# idealdiodeOR.net
KiCad netlist of a schematic drawn in Altium Designer
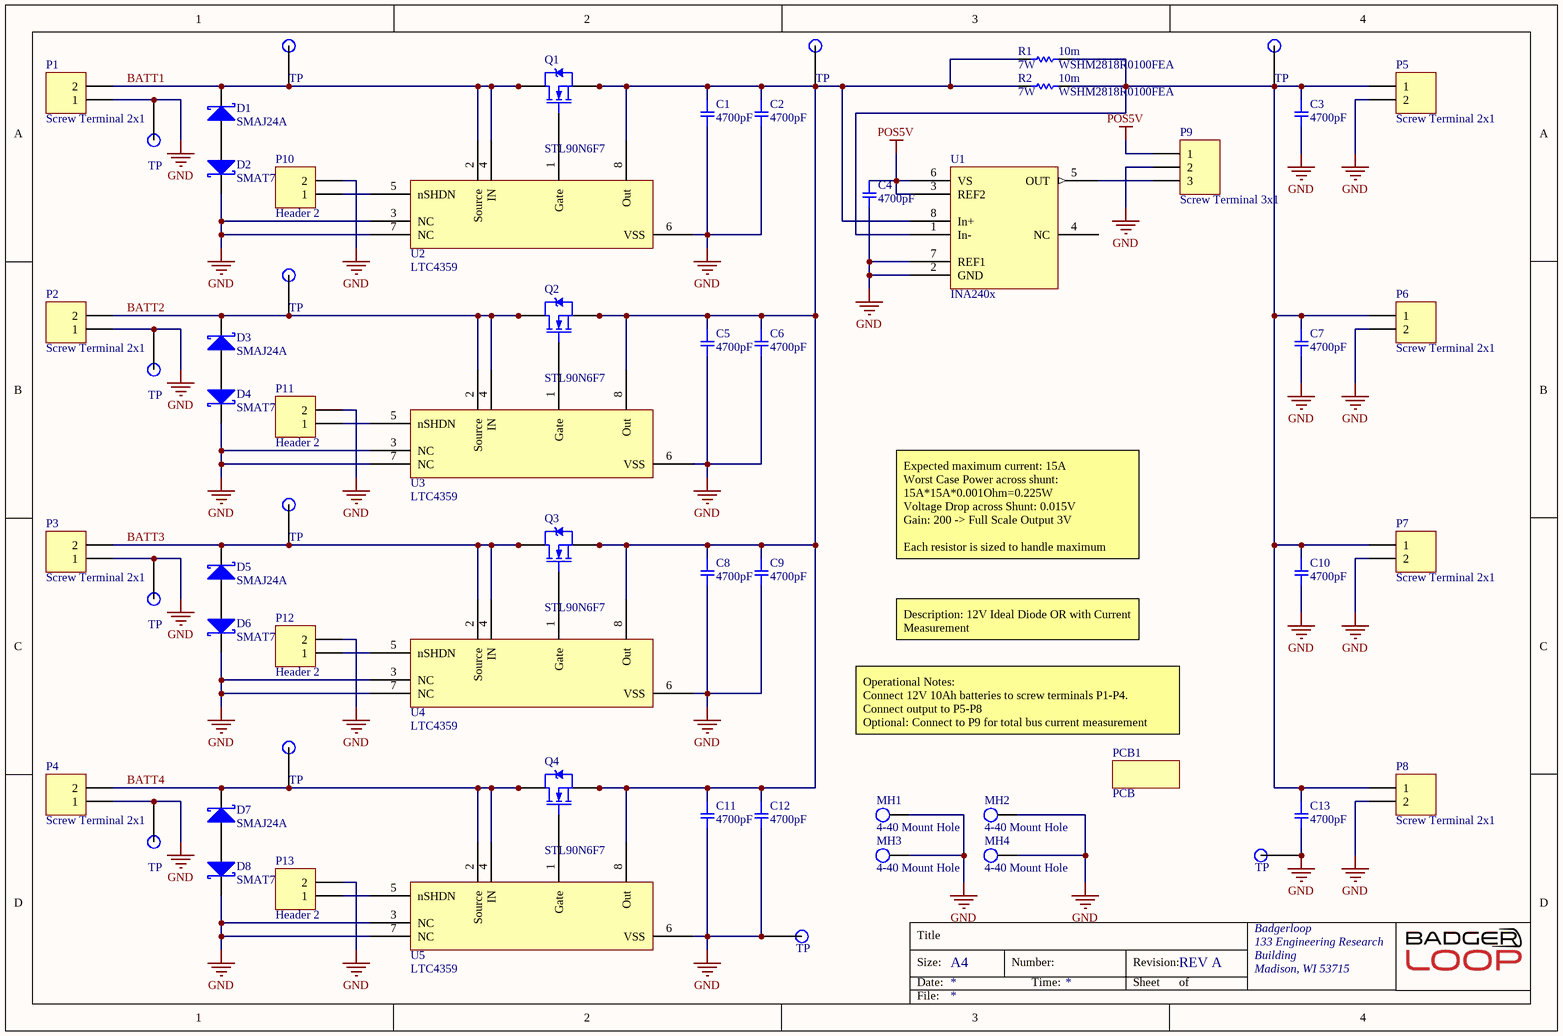
[diagram p0: idealdiodeOR.SchDoc]

(export (version "E")
  (design (tool "Eeschema 10.0.6"))
  (components
    (comp (ref "C1")
      (value "4700pF")
      (footprint "SMD-1206C")
      (description "CAP CER 4700PF 630V X7R 1206")
      (fields
        (field (name "PART NUMBER") "GCJ31BR72J472KXJ1L")
        (field (name "MANUFACTURER") "Murata Electronics North America")
      )
      (libsource (lib "capacitor") (part "GCJ31BR72J472KXJ1L"))
    )
    (comp (ref "C2")
      (value "4700pF")
      (footprint "SMD-1206C")
      (description "CAP CER 4700PF 630V X7R 1206")
      (fields
        (field (name "PART NUMBER") "GCJ31BR72J472KXJ1L")
        (field (name "MANUFACTURER") "Murata Electronics North America")
      )
      (libsource (lib "capacitor") (part "GCJ31BR72J472KXJ1L"))
    )
    (comp (ref "C3")
      (value "4700pF")
      (footprint "SMD-1206C")
      (description "CAP CER 4700PF 630V X7R 1206")
      (fields
        (field (name "PART NUMBER") "GCJ31BR72J472KXJ1L")
        (field (name "MANUFACTURER") "Murata Electronics North America")
      )
      (libsource (lib "capacitor") (part "GCJ31BR72J472KXJ1L"))
    )
    (comp (ref "C4")
      (value "4700pF")
      (footprint "SMD-1206C")
      (description "CAP CER 4700PF 630V X7R 1206")
      (fields
        (field (name "PART NUMBER") "GCJ31BR72J472KXJ1L")
        (field (name "MANUFACTURER") "Murata Electronics North America")
      )
      (libsource (lib "capacitor") (part "GCJ31BR72J472KXJ1L"))
    )
    (comp (ref "C5")
      (value "4700pF")
      (footprint "SMD-1206C")
      (description "CAP CER 4700PF 630V X7R 1206")
      (fields
        (field (name "PART NUMBER") "GCJ31BR72J472KXJ1L")
        (field (name "MANUFACTURER") "Murata Electronics North America")
      )
      (libsource (lib "capacitor") (part "GCJ31BR72J472KXJ1L"))
    )
    (comp (ref "C6")
      (value "4700pF")
      (footprint "SMD-1206C")
      (description "CAP CER 4700PF 630V X7R 1206")
      (fields
        (field (name "PART NUMBER") "GCJ31BR72J472KXJ1L")
        (field (name "MANUFACTURER") "Murata Electronics North America")
      )
      (libsource (lib "capacitor") (part "GCJ31BR72J472KXJ1L"))
    )
    (comp (ref "C7")
      (value "4700pF")
      (footprint "SMD-1206C")
      (description "CAP CER 4700PF 630V X7R 1206")
      (fields
        (field (name "PART NUMBER") "GCJ31BR72J472KXJ1L")
        (field (name "MANUFACTURER") "Murata Electronics North America")
      )
      (libsource (lib "capacitor") (part "GCJ31BR72J472KXJ1L"))
    )
    (comp (ref "C8")
      (value "4700pF")
      (footprint "SMD-1206C")
      (description "CAP CER 4700PF 630V X7R 1206")
      (fields
        (field (name "PART NUMBER") "GCJ31BR72J472KXJ1L")
        (field (name "MANUFACTURER") "Murata Electronics North America")
      )
      (libsource (lib "capacitor") (part "GCJ31BR72J472KXJ1L"))
    )
    (comp (ref "C9")
      (value "4700pF")
      (footprint "SMD-1206C")
      (description "CAP CER 4700PF 630V X7R 1206")
      (fields
        (field (name "PART NUMBER") "GCJ31BR72J472KXJ1L")
        (field (name "MANUFACTURER") "Murata Electronics North America")
      )
      (libsource (lib "capacitor") (part "GCJ31BR72J472KXJ1L"))
    )
    (comp (ref "C10")
      (value "4700pF")
      (footprint "SMD-1206C")
      (description "CAP CER 4700PF 630V X7R 1206")
      (fields
        (field (name "PART NUMBER") "GCJ31BR72J472KXJ1L")
        (field (name "MANUFACTURER") "Murata Electronics North America")
      )
      (libsource (lib "capacitor") (part "GCJ31BR72J472KXJ1L"))
    )
    (comp (ref "C11")
      (value "4700pF")
      (footprint "SMD-1206C")
      (description "CAP CER 4700PF 630V X7R 1206")
      (fields
        (field (name "PART NUMBER") "GCJ31BR72J472KXJ1L")
        (field (name "MANUFACTURER") "Murata Electronics North America")
      )
      (libsource (lib "capacitor") (part "GCJ31BR72J472KXJ1L"))
    )
    (comp (ref "C12")
      (value "4700pF")
      (footprint "SMD-1206C")
      (description "CAP CER 4700PF 630V X7R 1206")
      (fields
        (field (name "PART NUMBER") "GCJ31BR72J472KXJ1L")
        (field (name "MANUFACTURER") "Murata Electronics North America")
      )
      (libsource (lib "capacitor") (part "GCJ31BR72J472KXJ1L"))
    )
    (comp (ref "C13")
      (value "4700pF")
      (footprint "SMD-1206C")
      (description "CAP CER 4700PF 630V X7R 1206")
      (fields
        (field (name "PART NUMBER") "GCJ31BR72J472KXJ1L")
        (field (name "MANUFACTURER") "Murata Electronics North America")
      )
      (libsource (lib "capacitor") (part "GCJ31BR72J472KXJ1L"))
    )
    (comp (ref "D1")
      (value "SMAJ24A")
      (footprint "INDM5026X18N")
      (description "TVS DIODE 24V 38.9V DO214AC")
      (fields (field (name "MANUFACTURER") "LittelFuse Inc"))
      (libsource (lib "temp") (part "SMAJ24A"))
    )
    (comp (ref "D2")
      (value "SMAT70A")
      (footprint "SMAT70A")
      (description "TVS DIODE 70V 100V SMA")
      (fields (field (name "MANUFACTURER") "Diodes Incorporated"))
      (libsource (lib "temp") (part "SMAT70A"))
    )
    (comp (ref "D3")
      (value "SMAJ24A")
      (footprint "INDM5026X18N")
      (description "TVS DIODE 24V 38.9V DO214AC")
      (fields (field (name "MANUFACTURER") "LittelFuse Inc"))
      (libsource (lib "temp") (part "SMAJ24A"))
    )
    (comp (ref "D4")
      (value "SMAT70A")
      (footprint "SMAT70A")
      (description "TVS DIODE 70V 100V SMA")
      (fields (field (name "MANUFACTURER") "Diodes Incorporated"))
      (libsource (lib "temp") (part "SMAT70A"))
    )
    (comp (ref "D5")
      (value "SMAJ24A")
      (footprint "INDM5026X18N")
      (description "TVS DIODE 24V 38.9V DO214AC")
      (fields (field (name "MANUFACTURER") "LittelFuse Inc"))
      (libsource (lib "temp") (part "SMAJ24A"))
    )
    (comp (ref "D6")
      (value "SMAT70A")
      (footprint "SMAT70A")
      (description "TVS DIODE 70V 100V SMA")
      (fields (field (name "MANUFACTURER") "Diodes Incorporated"))
      (libsource (lib "temp") (part "SMAT70A"))
    )
    (comp (ref "D7")
      (value "SMAJ24A")
      (footprint "INDM5026X18N")
      (description "TVS DIODE 24V 38.9V DO214AC")
      (fields (field (name "MANUFACTURER") "LittelFuse Inc"))
      (libsource (lib "temp") (part "SMAJ24A"))
    )
    (comp (ref "D8")
      (value "SMAT70A")
      (footprint "SMAT70A")
      (description "TVS DIODE 70V 100V SMA")
      (fields (field (name "MANUFACTURER") "Diodes Incorporated"))
      (libsource (lib "temp") (part "SMAT70A"))
    )
    (comp (ref "MH1")
      (value "4-40 Mount Hole")
      (footprint "MH")
      (libsource (lib "misc") (part "4-40 Mount Hole"))
    )
    (comp (ref "MH2")
      (value "4-40 Mount Hole")
      (footprint "MH")
      (libsource (lib "misc") (part "4-40 Mount Hole"))
    )
    (comp (ref "MH3")
      (value "4-40 Mount Hole")
      (footprint "MH")
      (libsource (lib "misc") (part "4-40 Mount Hole"))
    )
    (comp (ref "MH4")
      (value "4-40 Mount Hole")
      (footprint "MH")
      (libsource (lib "misc") (part "4-40 Mount Hole"))
    )
    (comp (ref "P1")
      (value "Screw Terminal 2x1")
      (footprint "2POS TERM BLOCK")
      (description "Screw Terminal, 2-Pin")
      (libsource (lib "") (part "Screw Terminal 2x1_1"))
    )
    (comp (ref "P2")
      (value "Screw Terminal 2x1")
      (footprint "2POS TERM BLOCK")
      (description "Screw Terminal, 2-Pin")
      (libsource (lib "") (part "Screw Terminal 2x1_1"))
    )
    (comp (ref "P3")
      (value "Screw Terminal 2x1")
      (footprint "2POS TERM BLOCK")
      (description "Screw Terminal, 2-Pin")
      (libsource (lib "") (part "Screw Terminal 2x1_1"))
    )
    (comp (ref "P4")
      (value "Screw Terminal 2x1")
      (footprint "2POS TERM BLOCK")
      (description "Screw Terminal, 2-Pin")
      (libsource (lib "") (part "Screw Terminal 2x1_1"))
    )
    (comp (ref "P5")
      (value "Screw Terminal 2x1")
      (footprint "2POS TERM BLOCK")
      (description "Screw Terminal, 2-Pin")
      (libsource (lib "connector") (part "Screw Terminal 2x1"))
    )
    (comp (ref "P6")
      (value "Screw Terminal 2x1")
      (footprint "2POS TERM BLOCK")
      (description "Screw Terminal, 2-Pin")
      (libsource (lib "connector") (part "Screw Terminal 2x1"))
    )
    (comp (ref "P7")
      (value "Screw Terminal 2x1")
      (footprint "2POS TERM BLOCK")
      (description "Screw Terminal, 2-Pin")
      (libsource (lib "connector") (part "Screw Terminal 2x1"))
    )
    (comp (ref "P8")
      (value "Screw Terminal 2x1")
      (footprint "2POS TERM BLOCK")
      (description "Screw Terminal, 2-Pin")
      (libsource (lib "connector") (part "Screw Terminal 2x1"))
    )
    (comp (ref "P9")
      (value "Screw Terminal 3x1")
      (footprint "3POS TERM BLOCK")
      (description "Screw Terminal, 3-Pin")
      (fields (field (name "PUBLISHER") "Altium Limited"))
      (libsource (lib "connector") (part "Screw Terminal 3x1"))
    )
    (comp (ref "P10")
      (value "Header 2")
      (footprint "Pin Header 1x2 TH Pitch 2.54mm")
      (description "Header, 2-Pin")
      (fields (field (name "PUBLISHER") "Altium Limited"))
      (libsource (lib "altium-import") (part "root_2_Header 2_"))
    )
    (comp (ref "P11")
      (value "Header 2")
      (footprint "Pin Header 1x2 TH Pitch 2.54mm")
      (description "Header, 2-Pin")
      (fields (field (name "PUBLISHER") "Altium Limited"))
      (libsource (lib "altium-import") (part "root_2_Header 2_"))
    )
    (comp (ref "P12")
      (value "Header 2")
      (footprint "Pin Header 1x2 TH Pitch 2.54mm")
      (description "Header, 2-Pin")
      (fields (field (name "PUBLISHER") "Altium Limited"))
      (libsource (lib "altium-import") (part "root_2_Header 2_"))
    )
    (comp (ref "P13")
      (value "Header 2")
      (footprint "Pin Header 1x2 TH Pitch 2.54mm")
      (description "Header, 2-Pin")
      (fields (field (name "PUBLISHER") "Altium Limited"))
      (libsource (lib "altium-import") (part "root_2_Header 2_"))
    )
    (comp (ref "PCB1") (value "PCB") (footprint "PCB") (libsource (lib "temp") (part "PCB")))
    (comp (ref "Q1")
      (value "STL90N6F7")
      (footprint "DPAK228P991X238-4N")
      (description "MOSFET N-CH 60V 90A F7 8PWRFLAT")
      (fields (field (name "MANUFACTURER") "497-15913-2-ND"))
      (libsource (lib "temp") (part "STL90N6F7"))
    )
    (comp (ref "Q2")
      (value "STL90N6F7")
      (footprint "DPAK228P991X238-4N")
      (description "MOSFET N-CH 60V 90A F7 8PWRFLAT")
      (fields (field (name "MANUFACTURER") "497-15913-2-ND"))
      (libsource (lib "temp") (part "STL90N6F7"))
    )
    (comp (ref "Q3")
      (value "STL90N6F7")
      (footprint "DPAK228P991X238-4N")
      (description "MOSFET N-CH 60V 90A F7 8PWRFLAT")
      (fields (field (name "MANUFACTURER") "497-15913-2-ND"))
      (libsource (lib "temp") (part "STL90N6F7"))
    )
    (comp (ref "Q4")
      (value "STL90N6F7")
      (footprint "DPAK228P991X238-4N")
      (description "MOSFET N-CH 60V 90A F7 8PWRFLAT")
      (fields (field (name "MANUFACTURER") "497-15913-2-ND"))
      (libsource (lib "temp") (part "STL90N6F7"))
    )
    (comp (ref "R1")
      (value "WSHM2818R0100FEA")
      (footprint "CAPMP7146X15N")
      (description "RES 0.01 OHM 1% 7W 2818")
      (fields
        (field (name "MANUFACTURER") "Vishay Dale")
        (field (name "RESISTANCE") "10m")
        (field (name "POWER RATING") "7W")
      )
      (libsource (lib "temp") (part "WSHM2818R0100FEA"))
    )
    (comp (ref "R2")
      (value "WSHM2818R0100FEA")
      (footprint "CAPMP7146X15N")
      (description "RES 0.01 OHM 1% 7W 2818")
      (fields
        (field (name "MANUFACTURER") "Vishay Dale")
        (field (name "RESISTANCE") "10m")
        (field (name "POWER RATING") "7W")
      )
      (libsource (lib "temp") (part "WSHM2818R0100FEA"))
    )
    (comp (ref "TP1") (value "TP") (footprint "Test Point") (libsource (lib "misc") (part "TP")))
    (comp (ref "TP2") (value "TP") (footprint "Test Point") (libsource (lib "misc") (part "TP")))
    (comp (ref "TP3") (value "TP") (footprint "Test Point") (libsource (lib "misc") (part "TP")))
    (comp (ref "TP4") (value "TP") (footprint "Test Point") (libsource (lib "misc") (part "TP")))
    (comp (ref "TP5") (value "TP") (footprint "Test Point") (libsource (lib "misc") (part "TP")))
    (comp (ref "TP6") (value "TP") (footprint "Test Point") (libsource (lib "misc") (part "TP")))
    (comp (ref "TP7") (value "TP") (footprint "Test Point") (libsource (lib "misc") (part "TP")))
    (comp (ref "TP8") (value "TP") (footprint "Test Point") (libsource (lib "misc") (part "TP")))
    (comp (ref "TP9") (value "TP") (footprint "Test Point") (libsource (lib "misc") (part "TP")))
    (comp (ref "TP10") (value "TP") (footprint "Test Point") (libsource (lib "misc") (part "TP")))
    (comp (ref "TP11") (value "TP") (footprint "Test Point") (libsource (lib "misc") (part "TP")))
    (comp (ref "TP12") (value "TP") (footprint "Test Point") (libsource (lib "misc") (part "TP")))
    (comp (ref "U1")
      (value "INA240x")
      (footprint "SOIC127P600X175-8N")
      (description "IC AMP CURRENT SENSE 8-TSSOP")
      (fields (field (name "MANUFACTURER") "TI"))
      (libsource (lib "ic") (part "INA240x"))
    )
    (comp (ref "U2")
      (value "LTC4359")
      (footprint "8SOP")
      (description "IC OR CTRLR N+1 8MSOP")
      (fields (field (name "MANUFACTURER") "Analog Devices"))
      (libsource (lib "temp") (part "LTC4359"))
    )
    (comp (ref "U3")
      (value "LTC4359")
      (footprint "8SOP")
      (description "IC OR CTRLR N+1 8MSOP")
      (fields (field (name "MANUFACTURER") "Analog Devices"))
      (libsource (lib "temp") (part "LTC4359"))
    )
    (comp (ref "U4")
      (value "LTC4359")
      (footprint "8SOP")
      (description "IC OR CTRLR N+1 8MSOP")
      (fields (field (name "MANUFACTURER") "Analog Devices"))
      (libsource (lib "temp") (part "LTC4359"))
    )
    (comp (ref "U5")
      (value "LTC4359")
      (footprint "8SOP")
      (description "IC OR CTRLR N+1 8MSOP")
      (fields (field (name "MANUFACTURER") "Analog Devices"))
      (libsource (lib "temp") (part "LTC4359"))
    )
  )
  (nets
    (net (code "1") (name "/BATT1") (class "Default")
      (node (ref "D1") (pin "1") (pinfunction "A_1") (pintype "passive"))
      (node (ref "P1") (pin "2") (pinfunction "2_2") (pintype "passive"))
      (node (ref "Q1") (pin "5") (pinfunction "D_5") (pintype "passive"))
      (node (ref "Q1") (pin "6") (pinfunction "D_6") (pintype "passive"))
      (node (ref "Q1") (pin "7") (pinfunction "D_7") (pintype "passive"))
      (node (ref "Q1") (pin "8") (pinfunction "D_8") (pintype "passive"))
      (node (ref "TP1") (pin "1") (pinfunction "1_1") (pintype "passive"))
      (node (ref "U2") (pin "2") (pinfunction "Source_2") (pintype "passive"))
      (node (ref "U2") (pin "4") (pinfunction "IN_4") (pintype "passive"))
    )
    (net (code "2") (name "/BATT2") (class "Default")
      (node (ref "D3") (pin "1") (pinfunction "A_1") (pintype "passive"))
      (node (ref "P2") (pin "2") (pinfunction "2_2") (pintype "passive"))
      (node (ref "Q2") (pin "5") (pinfunction "D_5") (pintype "passive"))
      (node (ref "Q2") (pin "6") (pinfunction "D_6") (pintype "passive"))
      (node (ref "Q2") (pin "7") (pinfunction "D_7") (pintype "passive"))
      (node (ref "Q2") (pin "8") (pinfunction "D_8") (pintype "passive"))
      (node (ref "TP4") (pin "1") (pinfunction "1_1") (pintype "passive"))
      (node (ref "U3") (pin "2") (pinfunction "Source_2") (pintype "passive"))
      (node (ref "U3") (pin "4") (pinfunction "IN_4") (pintype "passive"))
    )
    (net (code "3") (name "/BATT3") (class "Default")
      (node (ref "D5") (pin "1") (pinfunction "A_1") (pintype "passive"))
      (node (ref "P3") (pin "2") (pinfunction "2_2") (pintype "passive"))
      (node (ref "Q3") (pin "5") (pinfunction "D_5") (pintype "passive"))
      (node (ref "Q3") (pin "6") (pinfunction "D_6") (pintype "passive"))
      (node (ref "Q3") (pin "7") (pinfunction "D_7") (pintype "passive"))
      (node (ref "Q3") (pin "8") (pinfunction "D_8") (pintype "passive"))
      (node (ref "TP6") (pin "1") (pinfunction "1_1") (pintype "passive"))
      (node (ref "U4") (pin "2") (pinfunction "Source_2") (pintype "passive"))
      (node (ref "U4") (pin "4") (pinfunction "IN_4") (pintype "passive"))
    )
    (net (code "4") (name "/BATT4") (class "Default")
      (node (ref "D7") (pin "1") (pinfunction "A_1") (pintype "passive"))
      (node (ref "P4") (pin "2") (pinfunction "2_2") (pintype "passive"))
      (node (ref "Q4") (pin "5") (pinfunction "D_5") (pintype "passive"))
      (node (ref "Q4") (pin "6") (pinfunction "D_6") (pintype "passive"))
      (node (ref "Q4") (pin "7") (pinfunction "D_7") (pintype "passive"))
      (node (ref "Q4") (pin "8") (pinfunction "D_8") (pintype "passive"))
      (node (ref "TP8") (pin "1") (pinfunction "1_1") (pintype "passive"))
      (node (ref "U5") (pin "2") (pinfunction "Source_2") (pintype "passive"))
      (node (ref "U5") (pin "4") (pinfunction "IN_4") (pintype "passive"))
    )
    (net (code "5") (name "GND") (class "Default")
      (node (ref "C1") (pin "2") (pinfunction "2_2") (pintype "passive"))
      (node (ref "C10") (pin "2") (pinfunction "2_2") (pintype "passive"))
      (node (ref "C11") (pin "2") (pinfunction "2_2") (pintype "passive"))
      (node (ref "C12") (pin "2") (pinfunction "2_2") (pintype "passive"))
      (node (ref "C13") (pin "2") (pinfunction "2_2") (pintype "passive"))
      (node (ref "C2") (pin "2") (pinfunction "2_2") (pintype "passive"))
      (node (ref "C3") (pin "2") (pinfunction "2_2") (pintype "passive"))
      (node (ref "C4") (pin "2") (pinfunction "2_2") (pintype "passive"))
      (node (ref "C5") (pin "2") (pinfunction "2_2") (pintype "passive"))
      (node (ref "C6") (pin "2") (pinfunction "2_2") (pintype "passive"))
      (node (ref "C7") (pin "2") (pinfunction "2_2") (pintype "passive"))
      (node (ref "C8") (pin "2") (pinfunction "2_2") (pintype "passive"))
      (node (ref "C9") (pin "2") (pinfunction "2_2") (pintype "passive"))
      (node (ref "D2") (pin "2") (pinfunction "K_2") (pintype "passive"))
      (node (ref "D4") (pin "2") (pinfunction "K_2") (pintype "passive"))
      (node (ref "D6") (pin "2") (pinfunction "K_2") (pintype "passive"))
      (node (ref "D8") (pin "2") (pinfunction "K_2") (pintype "passive"))
      (node (ref "MH1") (pin "2") (pinfunction "2_2") (pintype "passive"))
      (node (ref "MH2") (pin "2") (pinfunction "2_2") (pintype "passive"))
      (node (ref "MH3") (pin "2") (pinfunction "2_2") (pintype "passive"))
      (node (ref "MH4") (pin "2") (pinfunction "2_2") (pintype "passive"))
      (node (ref "P1") (pin "1") (pinfunction "1_1") (pintype "passive"))
      (node (ref "P10") (pin "2") (pinfunction "2_2") (pintype "passive"))
      (node (ref "P11") (pin "2") (pinfunction "2_2") (pintype "passive"))
      (node (ref "P12") (pin "2") (pinfunction "2_2") (pintype "passive"))
      (node (ref "P13") (pin "2") (pinfunction "2_2") (pintype "passive"))
      (node (ref "P2") (pin "1") (pinfunction "1_1") (pintype "passive"))
      (node (ref "P3") (pin "1") (pinfunction "1_1") (pintype "passive"))
      (node (ref "P4") (pin "1") (pinfunction "1_1") (pintype "passive"))
      (node (ref "P5") (pin "2") (pinfunction "2_2") (pintype "passive"))
      (node (ref "P6") (pin "2") (pinfunction "2_2") (pintype "passive"))
      (node (ref "P7") (pin "2") (pinfunction "2_2") (pintype "passive"))
      (node (ref "P8") (pin "2") (pinfunction "2_2") (pintype "passive"))
      (node (ref "P9") (pin "2") (pinfunction "2_2") (pintype "passive"))
      (node (ref "TP10") (pin "1") (pinfunction "1_1") (pintype "passive"))
      (node (ref "TP12") (pin "1") (pinfunction "1_1") (pintype "passive"))
      (node (ref "TP3") (pin "1") (pinfunction "1_1") (pintype "passive"))
      (node (ref "TP5") (pin "1") (pinfunction "1_1") (pintype "passive"))
      (node (ref "TP7") (pin "1") (pinfunction "1_1") (pintype "passive"))
      (node (ref "TP9") (pin "1") (pinfunction "1_1") (pintype "passive"))
      (node (ref "U1") (pin "2") (pinfunction "GND_2") (pintype "power_in"))
      (node (ref "U1") (pin "7") (pinfunction "REF1_7") (pintype "passive"))
      (node (ref "U2") (pin "3") (pinfunction "NC_3") (pintype "passive"))
      (node (ref "U2") (pin "6") (pinfunction "VSS_6") (pintype "passive"))
      (node (ref "U2") (pin "7") (pinfunction "NC_7") (pintype "passive"))
      (node (ref "U3") (pin "3") (pinfunction "NC_3") (pintype "passive"))
      (node (ref "U3") (pin "6") (pinfunction "VSS_6") (pintype "passive"))
      (node (ref "U3") (pin "7") (pinfunction "NC_7") (pintype "passive"))
      (node (ref "U4") (pin "3") (pinfunction "NC_3") (pintype "passive"))
      (node (ref "U4") (pin "6") (pinfunction "VSS_6") (pintype "passive"))
      (node (ref "U4") (pin "7") (pinfunction "NC_7") (pintype "passive"))
      (node (ref "U5") (pin "3") (pinfunction "NC_3") (pintype "passive"))
      (node (ref "U5") (pin "6") (pinfunction "VSS_6") (pintype "passive"))
      (node (ref "U5") (pin "7") (pinfunction "NC_7") (pintype "passive"))
    )
    (net (code "6") (name "Net-(D1-K)") (class "Default")
      (node (ref "D1") (pin "2") (pinfunction "K_2") (pintype "passive"))
      (node (ref "D2") (pin "1") (pinfunction "A_1") (pintype "passive"))
    )
    (net (code "7") (name "Net-(D3-K)") (class "Default")
      (node (ref "D3") (pin "2") (pinfunction "K_2") (pintype "passive"))
      (node (ref "D4") (pin "1") (pinfunction "A_1") (pintype "passive"))
    )
    (net (code "8") (name "Net-(D5-K)") (class "Default")
      (node (ref "D5") (pin "2") (pinfunction "K_2") (pintype "passive"))
      (node (ref "D6") (pin "1") (pinfunction "A_1") (pintype "passive"))
    )
    (net (code "9") (name "Net-(D7-K)") (class "Default")
      (node (ref "D7") (pin "2") (pinfunction "K_2") (pintype "passive"))
      (node (ref "D8") (pin "1") (pinfunction "A_1") (pintype "passive"))
    )
    (net (code "10") (name "Net-(Q1-G)") (class "Default")
      (node (ref "Q1") (pin "4") (pinfunction "G_4") (pintype "passive"))
      (node (ref "U2") (pin "1") (pinfunction "Gate_1") (pintype "passive"))
    )
    (net (code "11") (name "Net-(Q2-G)") (class "Default")
      (node (ref "Q2") (pin "4") (pinfunction "G_4") (pintype "passive"))
      (node (ref "U3") (pin "1") (pinfunction "Gate_1") (pintype "passive"))
    )
    (net (code "12") (name "Net-(Q3-G)") (class "Default")
      (node (ref "Q3") (pin "4") (pinfunction "G_4") (pintype "passive"))
      (node (ref "U4") (pin "1") (pinfunction "Gate_1") (pintype "passive"))
    )
    (net (code "13") (name "Net-(Q4-G)") (class "Default")
      (node (ref "Q4") (pin "4") (pinfunction "G_4") (pintype "passive"))
      (node (ref "U5") (pin "1") (pinfunction "Gate_1") (pintype "passive"))
    )
    (net (code "14") (name "Net-(U1-In+)") (class "Default")
      (node (ref "C1") (pin "1") (pinfunction "1_1") (pintype "passive"))
      (node (ref "C11") (pin "1") (pinfunction "1_1") (pintype "passive"))
      (node (ref "C12") (pin "1") (pinfunction "1_1") (pintype "passive"))
      (node (ref "C2") (pin "1") (pinfunction "1_1") (pintype "passive"))
      (node (ref "C5") (pin "1") (pinfunction "1_1") (pintype "passive"))
      (node (ref "C6") (pin "1") (pinfunction "1_1") (pintype "passive"))
      (node (ref "C8") (pin "1") (pinfunction "1_1") (pintype "passive"))
      (node (ref "C9") (pin "1") (pinfunction "1_1") (pintype "passive"))
      (node (ref "Q1") (pin "1") (pinfunction "S_1") (pintype "passive"))
      (node (ref "Q1") (pin "2") (pinfunction "S_2") (pintype "passive"))
      (node (ref "Q1") (pin "3") (pinfunction "S_3") (pintype "passive"))
      (node (ref "Q2") (pin "1") (pinfunction "S_1") (pintype "passive"))
      (node (ref "Q2") (pin "2") (pinfunction "S_2") (pintype "passive"))
      (node (ref "Q2") (pin "3") (pinfunction "S_3") (pintype "passive"))
      (node (ref "Q3") (pin "1") (pinfunction "S_1") (pintype "passive"))
      (node (ref "Q3") (pin "2") (pinfunction "S_2") (pintype "passive"))
      (node (ref "Q3") (pin "3") (pinfunction "S_3") (pintype "passive"))
      (node (ref "Q4") (pin "1") (pinfunction "S_1") (pintype "passive"))
      (node (ref "Q4") (pin "2") (pinfunction "S_2") (pintype "passive"))
      (node (ref "Q4") (pin "3") (pinfunction "S_3") (pintype "passive"))
      (node (ref "R1") (pin "1") (pinfunction "1_1") (pintype "passive"))
      (node (ref "R2") (pin "1") (pinfunction "1_1") (pintype "passive"))
      (node (ref "TP2") (pin "1") (pinfunction "1_1") (pintype "passive"))
      (node (ref "U1") (pin "8") (pinfunction "In+_8") (pintype "passive"))
      (node (ref "U2") (pin "8") (pinfunction "Out_8") (pintype "passive"))
      (node (ref "U3") (pin "8") (pinfunction "Out_8") (pintype "passive"))
      (node (ref "U4") (pin "8") (pinfunction "Out_8") (pintype "passive"))
      (node (ref "U5") (pin "8") (pinfunction "Out_8") (pintype "passive"))
    )
    (net (code "15") (name "Net-(U1-In-)") (class "Default")
      (node (ref "C10") (pin "1") (pinfunction "1_1") (pintype "passive"))
      (node (ref "C13") (pin "1") (pinfunction "1_1") (pintype "passive"))
      (node (ref "C3") (pin "1") (pinfunction "1_1") (pintype "passive"))
      (node (ref "C7") (pin "1") (pinfunction "1_1") (pintype "passive"))
      (node (ref "P5") (pin "1") (pinfunction "1_1") (pintype "passive"))
      (node (ref "P6") (pin "1") (pinfunction "1_1") (pintype "passive"))
      (node (ref "P7") (pin "1") (pinfunction "1_1") (pintype "passive"))
      (node (ref "P8") (pin "1") (pinfunction "1_1") (pintype "passive"))
      (node (ref "R1") (pin "2") (pinfunction "2_2") (pintype "passive"))
      (node (ref "R2") (pin "2") (pinfunction "2_2") (pintype "passive"))
      (node (ref "TP11") (pin "1") (pinfunction "1_1") (pintype "passive"))
      (node (ref "U1") (pin "1") (pinfunction "In-_1") (pintype "passive"))
    )
    (net (code "16") (name "Net-(U1-OUT)") (class "Default")
      (node (ref "P9") (pin "3") (pinfunction "3_3") (pintype "passive"))
      (node (ref "U1") (pin "5") (pinfunction "OUT_5") (pintype "output"))
    )
    (net (code "17") (name "Net-(U2-nSHDN)") (class "Default")
      (node (ref "P10") (pin "1") (pinfunction "1_1") (pintype "passive"))
      (node (ref "U2") (pin "5") (pinfunction "nSHDN_5") (pintype "passive"))
    )
    (net (code "18") (name "Net-(U3-nSHDN)") (class "Default")
      (node (ref "P11") (pin "1") (pinfunction "1_1") (pintype "passive"))
      (node (ref "U3") (pin "5") (pinfunction "nSHDN_5") (pintype "passive"))
    )
    (net (code "19") (name "Net-(U4-nSHDN)") (class "Default")
      (node (ref "P12") (pin "1") (pinfunction "1_1") (pintype "passive"))
      (node (ref "U4") (pin "5") (pinfunction "nSHDN_5") (pintype "passive"))
    )
    (net (code "20") (name "Net-(U5-nSHDN)") (class "Default")
      (node (ref "P13") (pin "1") (pinfunction "1_1") (pintype "passive"))
      (node (ref "U5") (pin "5") (pinfunction "nSHDN_5") (pintype "passive"))
    )
    (net (code "21") (name "POS5V") (class "Default")
      (node (ref "C4") (pin "1") (pinfunction "1_1") (pintype "passive"))
      (node (ref "P9") (pin "1") (pinfunction "1_1") (pintype "passive"))
      (node (ref "U1") (pin "3") (pinfunction "REF2_3") (pintype "passive"))
      (node (ref "U1") (pin "6") (pinfunction "VS_6") (pintype "power_in"))
    )
    (net (code "22") (name "unconnected-(U1-NC-Pad4)") (class "Default")
      (node (ref "U1") (pin "4") (pinfunction "NC_4") (pintype "passive"))
    )
  )
)
